# Test_Reg.net
KiCad netlist of a schematic drawn in EAGLE
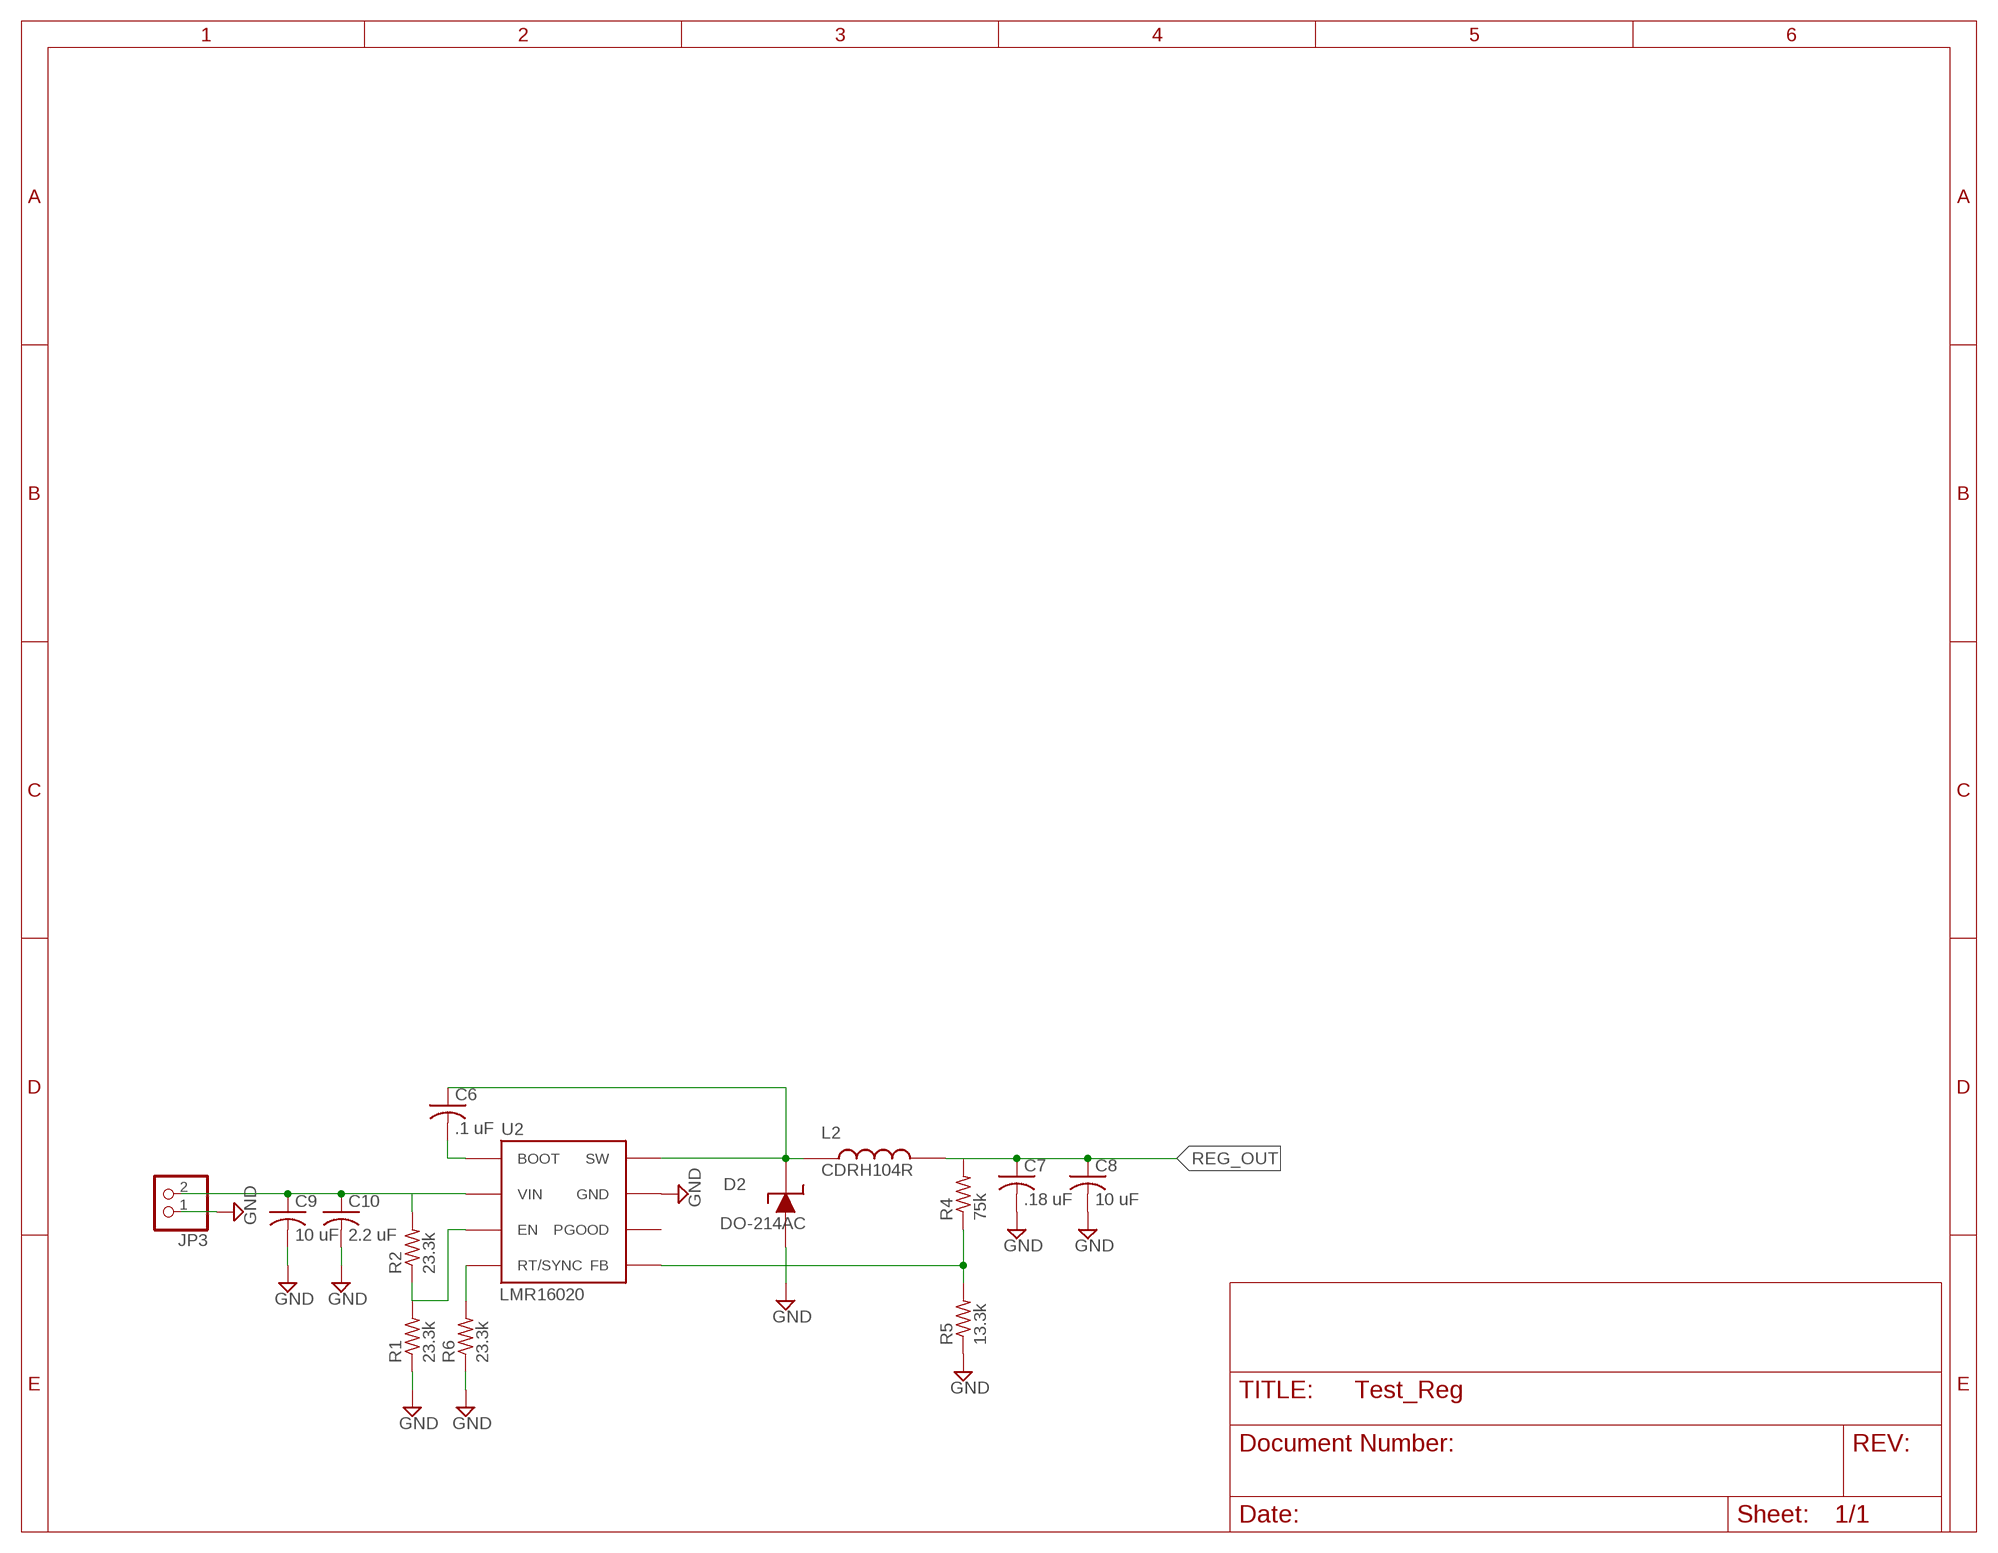
[diagram p0: schematic, sheet 1]

(export (version "E")
  (design (tool "Eeschema 10.0.6"))
  (components
    (comp (ref "C6")
      (value ".1 uF")
      (footprint "eagle-import:C0603")
      (libsource (lib "eagle-import") (part "C-USC0603"))
    )
    (comp (ref "C7")
      (value ".18 uF")
      (footprint "eagle-import:C0603")
      (libsource (lib "eagle-import") (part "C-USC0603"))
    )
    (comp (ref "C8")
      (value "10 uF")
      (footprint "eagle-import:C0603")
      (libsource (lib "eagle-import") (part "C-USC0603"))
    )
    (comp (ref "C9")
      (value "10 uF")
      (footprint "eagle-import:C1210")
      (libsource (lib "eagle-import") (part "C-USC1210"))
    )
    (comp (ref "C10")
      (value "2.2 uF")
      (footprint "eagle-import:C1210")
      (libsource (lib "eagle-import") (part "C-USC1210"))
    )
    (comp (ref "D2")
      (value "DO-214AC")
      (footprint "eagle-import:DO-214AC")
      (libsource (lib "eagle-import") (part "DO-214AC"))
    )
    (comp (ref "JP3")
      (value "PINHD-1X2")
      (footprint "eagle-import:1X02")
      (libsource (lib "eagle-import") (part "PINHD-1X2"))
    )
    (comp (ref "L2")
      (value "CDRH104R")
      (footprint "eagle-import:CDRH104R")
      (libsource (lib "eagle-import") (part "CDRH104R"))
    )
    (comp (ref "R1")
      (value "23.3k")
      (footprint "eagle-import:R0603")
      (libsource (lib "eagle-import") (part "R-US_R0603"))
    )
    (comp (ref "R2")
      (value "23.3k")
      (footprint "eagle-import:R0603")
      (libsource (lib "eagle-import") (part "R-US_R0603"))
    )
    (comp (ref "R4")
      (value "75k")
      (footprint "eagle-import:R0603")
      (libsource (lib "eagle-import") (part "R-US_R0603"))
    )
    (comp (ref "R5")
      (value "13.3k")
      (footprint "eagle-import:R0603")
      (libsource (lib "eagle-import") (part "R-US_R0603"))
    )
    (comp (ref "R6")
      (value "23.3k")
      (footprint "eagle-import:R0603")
      (libsource (lib "eagle-import") (part "R-US_R0603"))
    )
    (comp (ref "U2")
      (value "LMR16020")
      (footprint "eagle-import:SO8")
      (libsource (lib "eagle-import") (part "LMR16020"))
    )
  )
  (nets
    (net (code "1") (name "GND") (class "Default")
      (node (ref "C10") (pin "2") (pinfunction "2_2") (pintype "passive"))
      (node (ref "C7") (pin "2") (pinfunction "2_2") (pintype "passive"))
      (node (ref "C8") (pin "2") (pinfunction "2_2") (pintype "passive"))
      (node (ref "C9") (pin "2") (pinfunction "2_2") (pintype "passive"))
      (node (ref "D2") (pin "P$1") (pinfunction "P$1_P$1") (pintype "bidirectional"))
      (node (ref "JP3") (pin "1") (pinfunction "1_1") (pintype "passive"))
      (node (ref "R1") (pin "1") (pinfunction "1_1") (pintype "passive"))
      (node (ref "R5") (pin "1") (pinfunction "1_1") (pintype "passive"))
      (node (ref "R6") (pin "1") (pinfunction "1_1") (pintype "passive"))
      (node (ref "U2") (pin "P$7") (pinfunction "GND_P$7") (pintype "bidirectional"))
      (node (ref "U2") (pin "PAD") (pinfunction "GND_PAD") (pintype "bidirectional"))
    )
    (net (code "2") (name "Net-(U2-BOOT)") (class "Default")
      (node (ref "C6") (pin "2") (pinfunction "2_2") (pintype "passive"))
      (node (ref "U2") (pin "P$1") (pinfunction "BOOT_P$1") (pintype "bidirectional"))
    )
    (net (code "3") (name "Net-(U2-EN)") (class "Default")
      (node (ref "R1") (pin "2") (pinfunction "2_2") (pintype "passive"))
      (node (ref "R2") (pin "1") (pinfunction "1_1") (pintype "passive"))
      (node (ref "U2") (pin "P$3") (pinfunction "EN_P$3") (pintype "bidirectional"))
    )
    (net (code "4") (name "Net-(U2-FB)") (class "Default")
      (node (ref "R4") (pin "1") (pinfunction "1_1") (pintype "passive"))
      (node (ref "R5") (pin "2") (pinfunction "2_2") (pintype "passive"))
      (node (ref "U2") (pin "P$5") (pinfunction "FB_P$5") (pintype "bidirectional"))
    )
    (net (code "5") (name "Net-(U2-RT{slash}SYNC)") (class "Default")
      (node (ref "R6") (pin "2") (pinfunction "2_2") (pintype "passive"))
      (node (ref "U2") (pin "P$4") (pinfunction "RT/SYNC_P$4") (pintype "bidirectional"))
    )
    (net (code "6") (name "Net-(U2-SW)") (class "Default")
      (node (ref "C6") (pin "1") (pinfunction "1_1") (pintype "passive"))
      (node (ref "D2") (pin "P$2") (pinfunction "P$2_P$2") (pintype "bidirectional"))
      (node (ref "L2") (pin "P$1") (pinfunction "P$1_P$1") (pintype "bidirectional"))
      (node (ref "U2") (pin "P$8") (pinfunction "SW_P$8") (pintype "bidirectional"))
    )
    (net (code "7") (name "Net-(U2-VIN)") (class "Default")
      (node (ref "C10") (pin "1") (pinfunction "1_1") (pintype "passive"))
      (node (ref "C9") (pin "1") (pinfunction "1_1") (pintype "passive"))
      (node (ref "JP3") (pin "2") (pinfunction "2_2") (pintype "passive"))
      (node (ref "R2") (pin "2") (pinfunction "2_2") (pintype "passive"))
      (node (ref "U2") (pin "P$2") (pinfunction "VIN_P$2") (pintype "bidirectional"))
    )
    (net (code "8") (name "REG_OUT") (class "Default")
      (node (ref "C7") (pin "1") (pinfunction "1_1") (pintype "passive"))
      (node (ref "C8") (pin "1") (pinfunction "1_1") (pintype "passive"))
      (node (ref "L2") (pin "P$2") (pinfunction "P$2_P$2") (pintype "bidirectional"))
      (node (ref "R4") (pin "2") (pinfunction "2_2") (pintype "passive"))
    )
    (net (code "9") (name "unconnected-(U2-PGOOD-PadP$6)") (class "Default")
      (node (ref "U2") (pin "P$6") (pinfunction "PGOOD_P$6") (pintype "bidirectional"))
    )
  )
)
